# OpenModemV2_rx.net
KiCad netlist of a schematic drawn in EAGLE
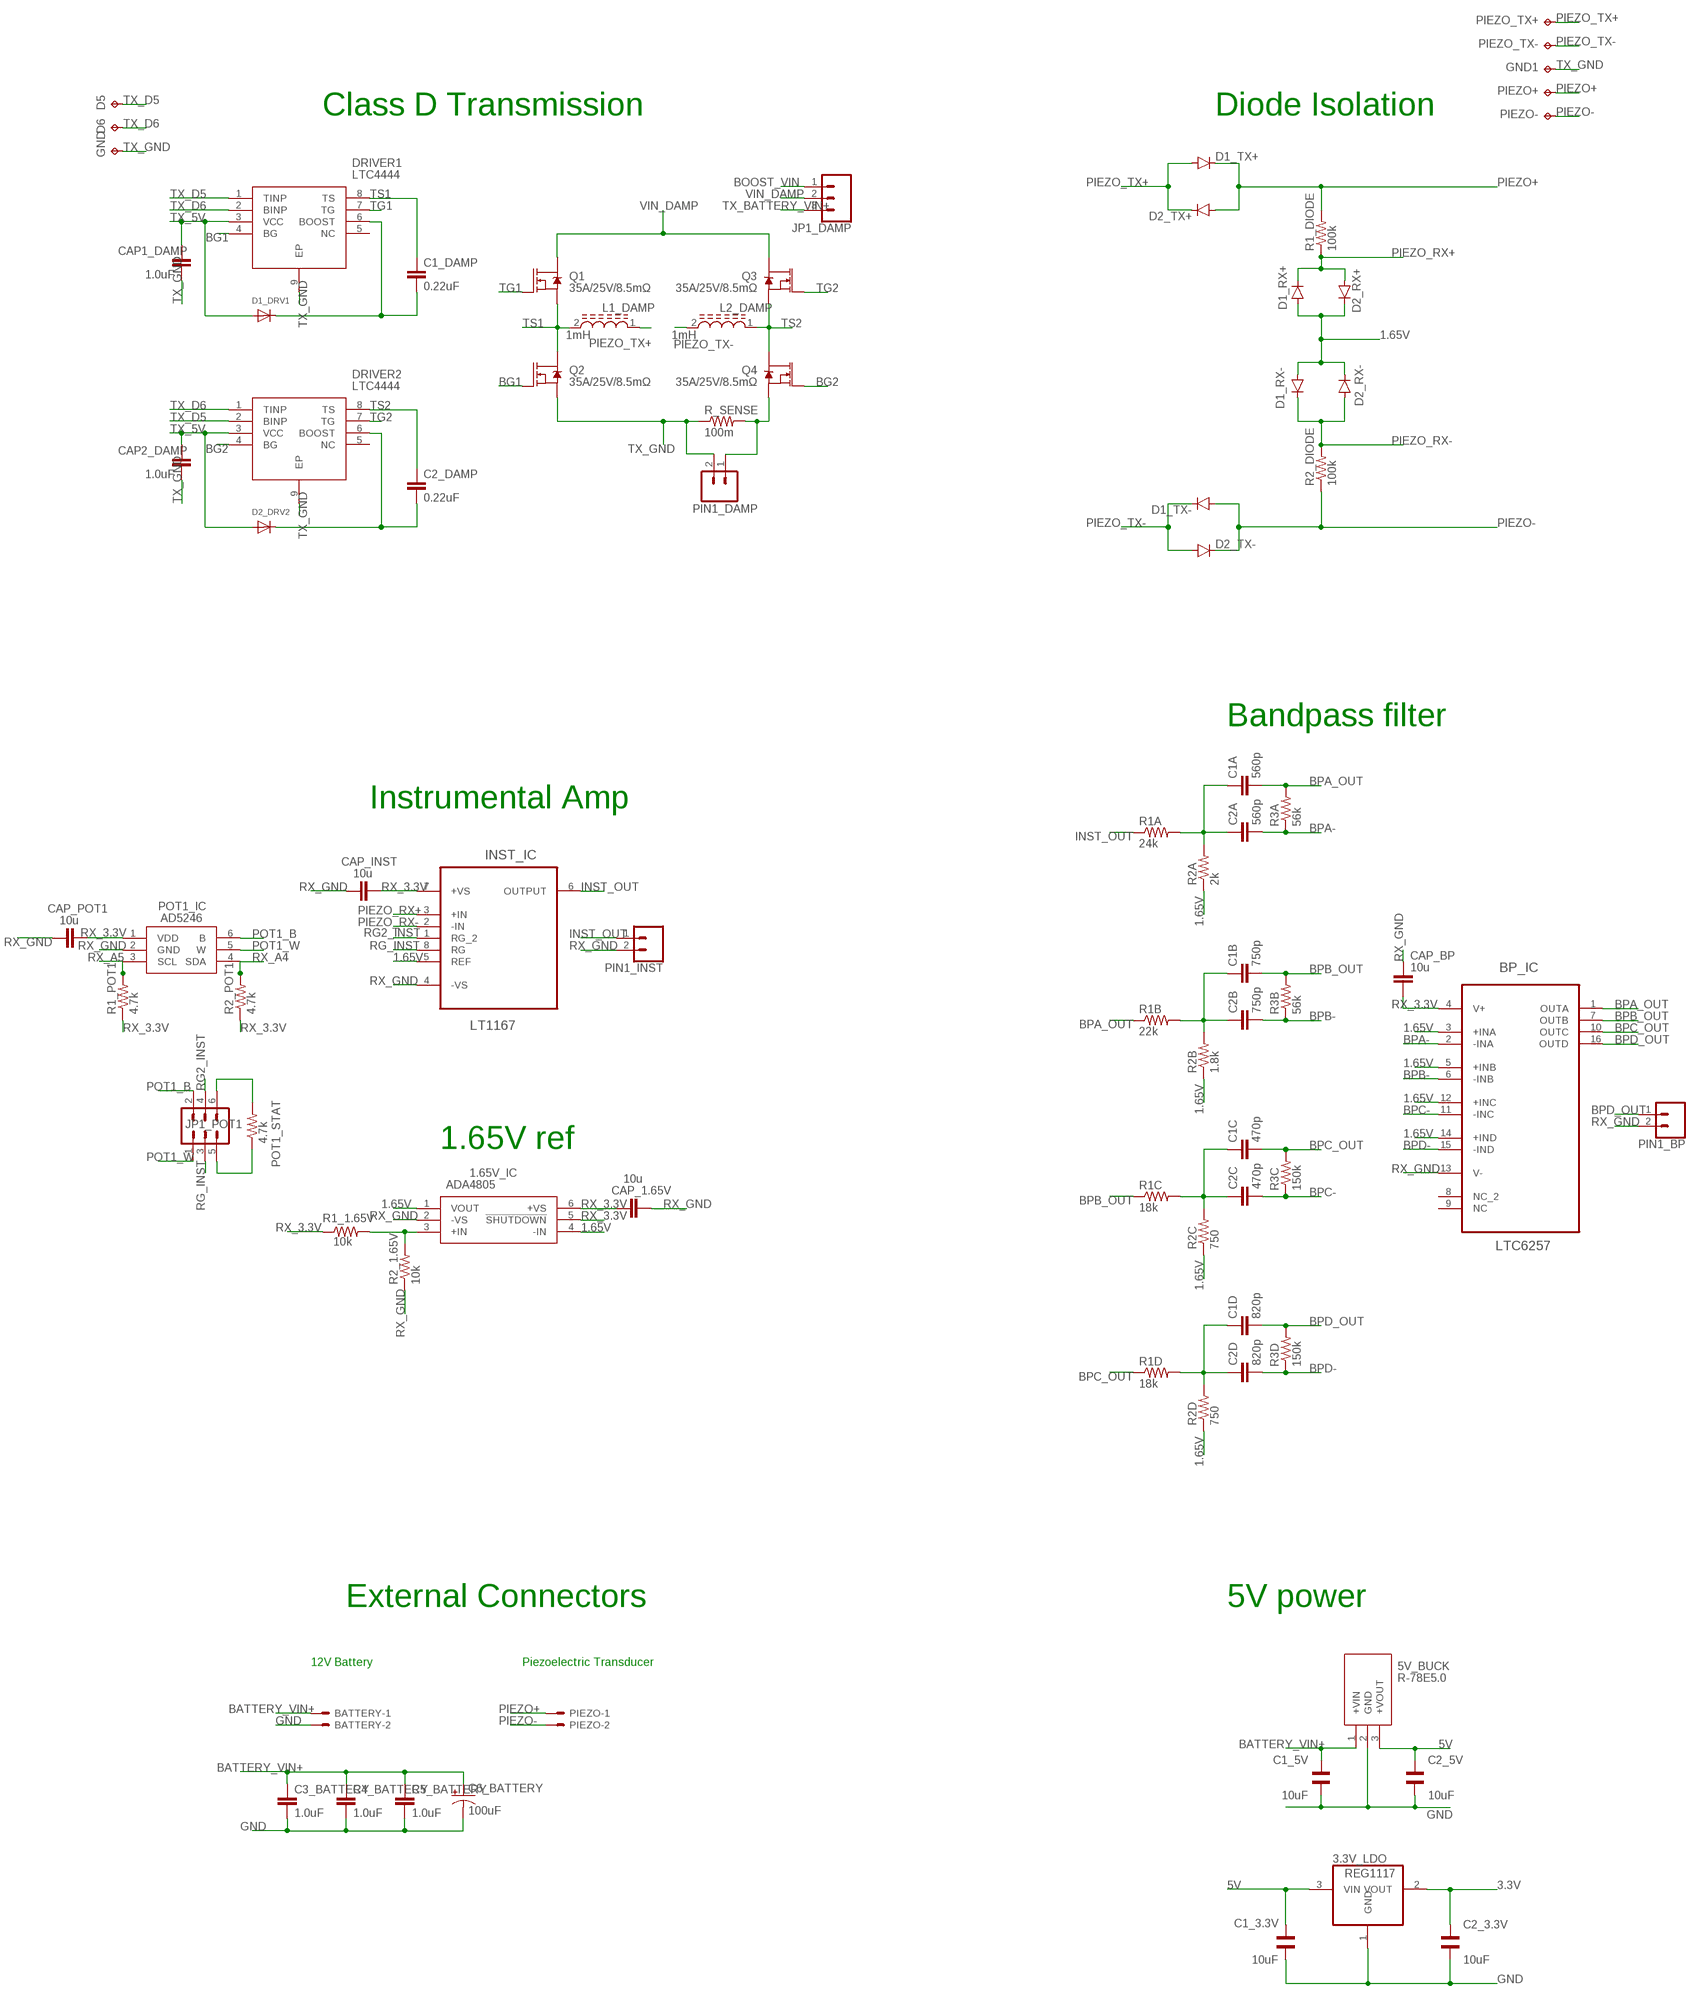
[diagram p0: schematic, sheet 1, part 1 of 2]
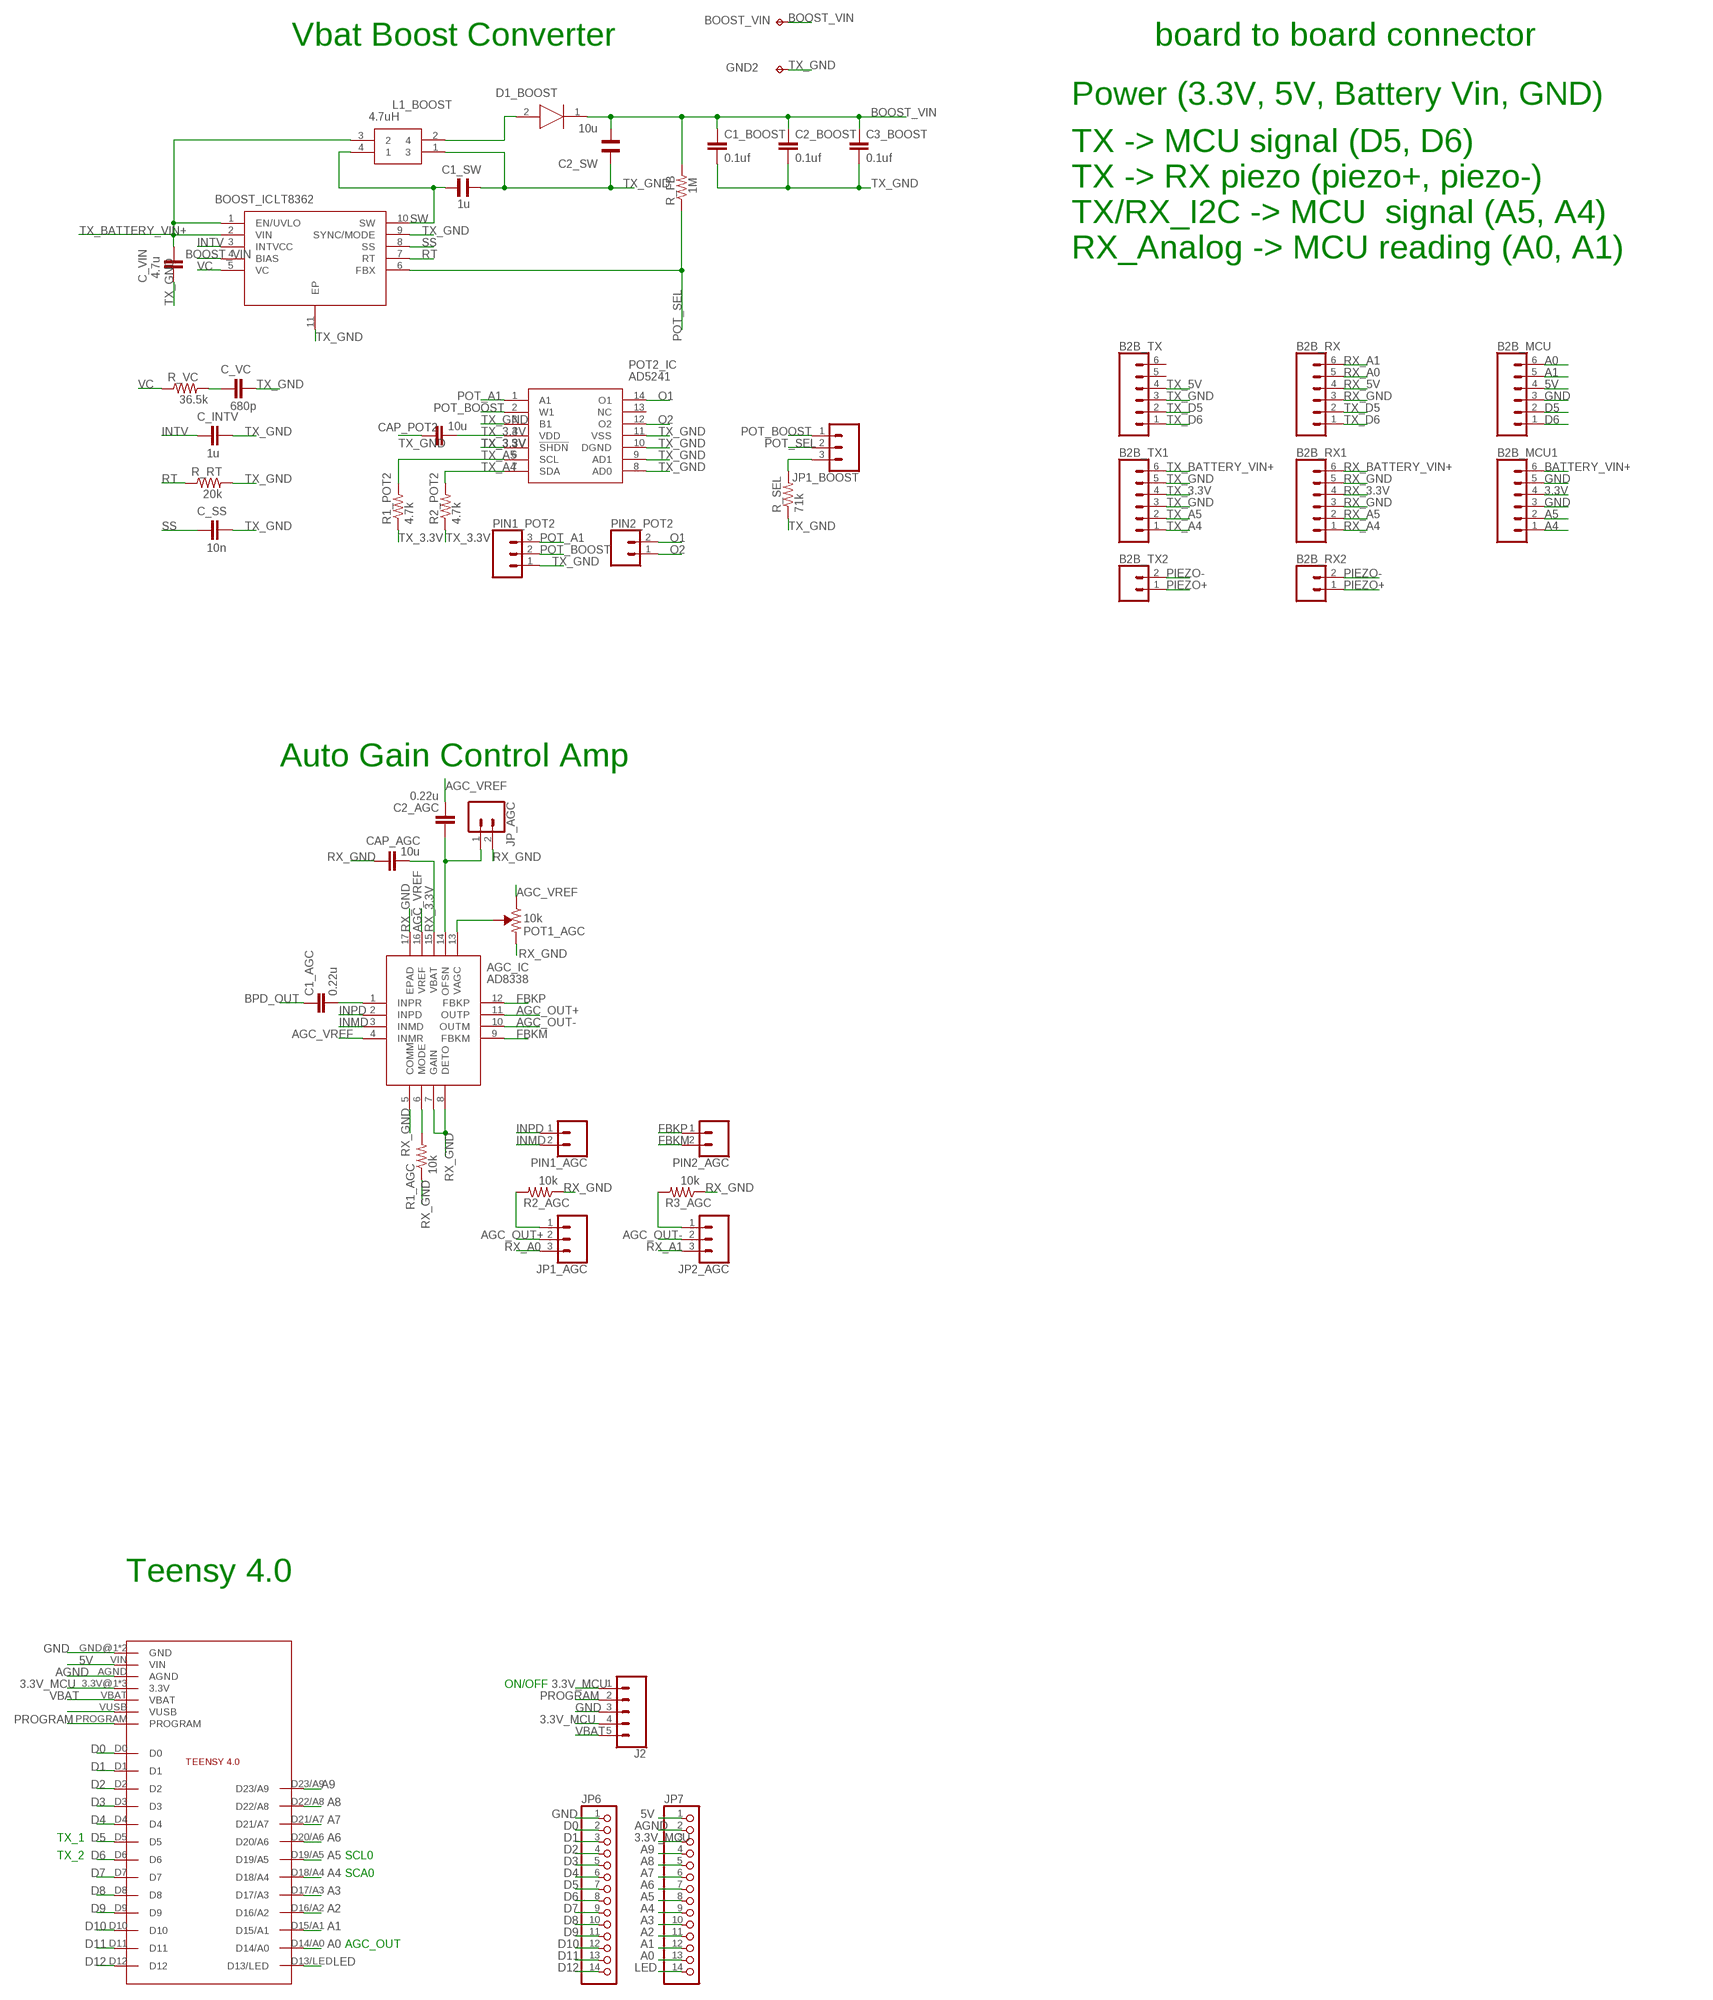
[diagram p1: schematic, sheet 1, part 2 of 2]

(export (version "E")
  (design (tool "Eeschema 10.0.6"))
  (components
    (comp (ref "1.65V_IC")
      (value "ADA4805")
      (footprint "eagle-import:SOT95P280X145-6N")
      (fields
        (field (name "MANUFACTURER_PART_NUMBER") "ADA4805-1ARJZ-R7")
        (field (name "MOUSER_PART_NUMBER") "584-ADA4805-1ARJZ-R7")
      )
      (libsource (lib "eagle-import") (part "ADA4805-1ARJZ-R7"))
    )
    (comp (ref "3.3V_LDO")
      (value "REG1117")
      (footprint "eagle-import:SOT223")
      (libsource (lib "eagle-import") (part "REG1117"))
    )
    (comp (ref "5V_BUCK")
      (value "R-78E5.0")
      (footprint "eagle-import:R-78E5.0-1.0")
      (fields
        (field (name "MANUFACTURER_PART_NUMBER") "R-78E5.0-1.0")
        (field (name "MOUSER_PART_NUMBER") "919-R-78E5.0-1.0")
      )
      (libsource (lib "eagle-import") (part "R-78E5.0-1.0"))
    )
    (comp (ref "AGC_IC")
      (value "AD8338")
      (footprint "eagle-import:QFN50P300X300X80-17N")
      (fields
        (field (name "MANUFACTURER_PART_NUMBER") "AD8338ACPZ-R7")
        (field (name "MOUSER_PART_NUMBER") "584-AD8338ACPZ-R7")
      )
      (libsource (lib "eagle-import") (part "AD8338ACPZ-R7"))
    )
    (comp (ref "B2B_MCU")
      (value "CONN_06SILK_FEMALE_PTH")
      (footprint "eagle-import:1X06")
      (libsource (lib "eagle-import") (part "CONN_06SILK_FEMALE_PTH"))
    )
    (comp (ref "B2B_MCU1")
      (value "CONN_06SILK_FEMALE_PTH")
      (footprint "eagle-import:1X06")
      (libsource (lib "eagle-import") (part "CONN_06SILK_FEMALE_PTH"))
    )
    (comp (ref "B2B_RX")
      (value "CONN_06SILK_FEMALE_PTH")
      (footprint "eagle-import:1X06")
      (libsource (lib "eagle-import") (part "CONN_06SILK_FEMALE_PTH"))
    )
    (comp (ref "B2B_RX1")
      (value "CONN_06SILK_FEMALE_PTH")
      (footprint "eagle-import:1X06")
      (libsource (lib "eagle-import") (part "CONN_06SILK_FEMALE_PTH"))
    )
    (comp (ref "B2B_RX2")
      (value "CONN_02")
      (footprint "eagle-import:1X02")
      (libsource (lib "eagle-import") (part "CONN_02"))
    )
    (comp (ref "B2B_TX")
      (value "CONN_06SILK_FEMALE_PTH")
      (footprint "eagle-import:1X06")
      (libsource (lib "eagle-import") (part "CONN_06SILK_FEMALE_PTH"))
    )
    (comp (ref "B2B_TX1")
      (value "CONN_06SILK_FEMALE_PTH")
      (footprint "eagle-import:1X06")
      (libsource (lib "eagle-import") (part "CONN_06SILK_FEMALE_PTH"))
    )
    (comp (ref "B2B_TX2")
      (value "CONN_02")
      (footprint "eagle-import:1X02")
      (libsource (lib "eagle-import") (part "CONN_02"))
    )
    (comp (ref "BATTERY")
      (value "22-27-2021-02")
      (footprint "eagle-import:6410-02")
      (fields (field (name "MF") "MOLEX"))
      (libsource (lib "eagle-import") (part "22-?-0227-2021"))
    )
    (comp (ref "BOOST_IC")
      (value "LT8362")
      (footprint "eagle-import:SON50P300X300X80-11N")
      (fields
        (field (name "MANUFACTURER_PART_NUMBER") "LT8362EDD#PBF")
        (field (name "MOUSER_PART_NUMBER") "584-LT8362EDDPBF")
      )
      (libsource (lib "eagle-import") (part "LT8362EDD#PBF"))
    )
    (comp (ref "BOOST_VIN")
      (value "TPPAD1-13")
      (footprint "eagle-import:P1-13")
      (libsource (lib "eagle-import") (part "TPPAD1-13"))
    )
    (comp (ref "BP_IC")
      (value "LTC6257")
      (footprint "eagle-import:SOP50P490X110-16N")
      (fields (field (name "MPN") "LTC6257CMS#PBF"))
      (libsource (lib "eagle-import") (part "LTC6257CMSPBF"))
    )
    (comp (ref "C1A")
      (value "560p")
      (footprint "eagle-import:C0402")
      (libsource (lib "eagle-import") (part "CC0402"))
    )
    (comp (ref "C1B")
      (value "750p")
      (footprint "eagle-import:C0402")
      (libsource (lib "eagle-import") (part "CC0402"))
    )
    (comp (ref "C1C")
      (value "470p")
      (footprint "eagle-import:C0402")
      (libsource (lib "eagle-import") (part "CC0402"))
    )
    (comp (ref "C1D")
      (value "820p")
      (footprint "eagle-import:C0402")
      (libsource (lib "eagle-import") (part "CC0402"))
    )
    (comp (ref "C1_3.3V")
      (value "10uF")
      (footprint "eagle-import:WCAP-CSGP_0603_REFLOW")
      (libsource (lib "eagle-import") (part "WCAP-CSGP_0603_REFLOW_885012006001"))
    )
    (comp (ref "C1_5V")
      (value "10uF")
      (footprint "eagle-import:WCAP-CSGP_0603_REFLOW")
      (libsource (lib "eagle-import") (part "WCAP-CSGP_0603_REFLOW_885012006001"))
    )
    (comp (ref "C1_AGC")
      (value "0.22u")
      (footprint "eagle-import:C0402")
      (libsource (lib "eagle-import") (part "CC0402"))
    )
    (comp (ref "C1_BOOST")
      (value "0.1uf")
      (footprint "eagle-import:0805")
      (libsource (lib "eagle-import") (part "1.0UF-0805-25V-(+80/-20%)"))
    )
    (comp (ref "C1_DAMP")
      (value "0.22uF")
      (footprint "eagle-import:0603")
      (libsource (lib "eagle-import") (part "0.22UF-0603-25V-10%"))
    )
    (comp (ref "C1_SW")
      (value "1u")
      (footprint "eagle-import:WCAP-CSGP_1206")
      (libsource (lib "eagle-import") (part "WCAP-CSGP_1206_885012008001"))
    )
    (comp (ref "C2A")
      (value "560p")
      (footprint "eagle-import:C0402")
      (libsource (lib "eagle-import") (part "CC0402"))
    )
    (comp (ref "C2B")
      (value "750p")
      (footprint "eagle-import:C0402")
      (libsource (lib "eagle-import") (part "CC0402"))
    )
    (comp (ref "C2C")
      (value "470p")
      (footprint "eagle-import:C0402")
      (libsource (lib "eagle-import") (part "CC0402"))
    )
    (comp (ref "C2D")
      (value "820p")
      (footprint "eagle-import:C0402")
      (libsource (lib "eagle-import") (part "CC0402"))
    )
    (comp (ref "C2_3.3V")
      (value "10uF")
      (footprint "eagle-import:WCAP-CSGP_0603_REFLOW")
      (libsource (lib "eagle-import") (part "WCAP-CSGP_0603_REFLOW_885012006001"))
    )
    (comp (ref "C2_5V")
      (value "10uF")
      (footprint "eagle-import:WCAP-CSGP_0603_REFLOW")
      (libsource (lib "eagle-import") (part "WCAP-CSGP_0603_REFLOW_885012006001"))
    )
    (comp (ref "C2_AGC")
      (value "0.22u")
      (footprint "eagle-import:C0402")
      (libsource (lib "eagle-import") (part "CC0402"))
    )
    (comp (ref "C2_BOOST")
      (value "0.1uf")
      (footprint "eagle-import:0805")
      (libsource (lib "eagle-import") (part "1.0UF-0805-25V-(+80/-20%)"))
    )
    (comp (ref "C2_DAMP")
      (value "0.22uF")
      (footprint "eagle-import:0603")
      (libsource (lib "eagle-import") (part "0.22UF-0603-25V-10%"))
    )
    (comp (ref "C2_SW")
      (value "10u")
      (footprint "eagle-import:WCAP-CSGP_1206")
      (libsource (lib "eagle-import") (part "WCAP-CSGP_1206_885012008001"))
    )
    (comp (ref "C3_BATTERY")
      (value "1.0uF")
      (footprint "eagle-import:0805")
      (libsource (lib "eagle-import") (part "1.0UF-0805-25V-(+80/-20%)"))
    )
    (comp (ref "C3_BOOST")
      (value "0.1uf")
      (footprint "eagle-import:0805")
      (libsource (lib "eagle-import") (part "1.0UF-0805-25V-(+80/-20%)"))
    )
    (comp (ref "C4_BATTERY")
      (value "1.0uF")
      (footprint "eagle-import:0805")
      (libsource (lib "eagle-import") (part "1.0UF-0805-25V-(+80/-20%)"))
    )
    (comp (ref "C5_BATTERY")
      (value "1.0uF")
      (footprint "eagle-import:0805")
      (libsource (lib "eagle-import") (part "1.0UF-0805-25V-(+80/-20%)"))
    )
    (comp (ref "C6_BATTERY")
      (value "100uF")
      (footprint "eagle-import:PANASONIC_D")
      (libsource (lib "eagle-import") (part "100UF-POLAR-25V-20%(ELEC)"))
    )
    (comp (ref "CAP1_DAMP")
      (value "1.0uF")
      (footprint "eagle-import:0603")
      (libsource (lib "eagle-import") (part "1.0UF-0603-16V-10%"))
    )
    (comp (ref "CAP2_DAMP")
      (value "1.0uF")
      (footprint "eagle-import:0603")
      (libsource (lib "eagle-import") (part "1.0UF-0603-16V-10%"))
    )
    (comp (ref "CAP_1.65V")
      (value "10u")
      (footprint "eagle-import:C0402")
      (libsource (lib "eagle-import") (part "CC0402"))
    )
    (comp (ref "CAP_AGC")
      (value "10u")
      (footprint "eagle-import:C0402")
      (libsource (lib "eagle-import") (part "CC0402"))
    )
    (comp (ref "CAP_BP")
      (value "10u")
      (footprint "eagle-import:C0402")
      (libsource (lib "eagle-import") (part "CC0402"))
    )
    (comp (ref "CAP_INST")
      (value "10u")
      (footprint "eagle-import:C0402")
      (libsource (lib "eagle-import") (part "CC0402"))
    )
    (comp (ref "CAP_POT1")
      (value "10u")
      (footprint "eagle-import:C0402")
      (libsource (lib "eagle-import") (part "CC0402"))
    )
    (comp (ref "CAP_POT2")
      (value "10u")
      (footprint "eagle-import:C0402")
      (libsource (lib "eagle-import") (part "CC0402"))
    )
    (comp (ref "C_INTV")
      (value "1u")
      (footprint "eagle-import:C0402")
      (libsource (lib "eagle-import") (part "CC0402"))
    )
    (comp (ref "C_SS")
      (value "10n")
      (footprint "eagle-import:C0402")
      (libsource (lib "eagle-import") (part "CC0402"))
    )
    (comp (ref "C_VC")
      (value "680p")
      (footprint "eagle-import:C0402")
      (libsource (lib "eagle-import") (part "CC0402"))
    )
    (comp (ref "C_VIN")
      (value "4.7u")
      (footprint "eagle-import:C0402")
      (libsource (lib "eagle-import") (part "CC0402"))
    )
    (comp (ref "D1_BOOST")
      (value "DFLS260-7")
      (footprint "eagle-import:POWERDI123")
      (fields (field (name "MOUSER_PART_NUMBER") "621-DFLS260-7"))
      (libsource (lib "eagle-import") (part "DFLS260-7"))
    )
    (comp (ref "D1_DRV1")
      (value "DIODESOD-323F")
      (footprint "eagle-import:SOD-323F")
      (libsource (lib "eagle-import") (part "DIODESOD-323F"))
    )
    (comp (ref "D1_RX+")
      (value "DIODE-SOD523")
      (footprint "eagle-import:SOD523")
      (libsource (lib "eagle-import") (part "DIODE-SOD523"))
    )
    (comp (ref "D1_RX-")
      (value "DIODE-SOD523")
      (footprint "eagle-import:SOD523")
      (libsource (lib "eagle-import") (part "DIODE-SOD523"))
    )
    (comp (ref "D1_TX+")
      (value "DIODE-SOD523")
      (footprint "eagle-import:SOD523")
      (libsource (lib "eagle-import") (part "DIODE-SOD523"))
    )
    (comp (ref "D1_TX-")
      (value "DIODE-SOD523")
      (footprint "eagle-import:SOD523")
      (libsource (lib "eagle-import") (part "DIODE-SOD523"))
    )
    (comp (ref "D2_DRV2")
      (value "DIODESOD-323F")
      (footprint "eagle-import:SOD-323F")
      (libsource (lib "eagle-import") (part "DIODESOD-323F"))
    )
    (comp (ref "D2_RX+")
      (value "DIODE-SOD523")
      (footprint "eagle-import:SOD523")
      (libsource (lib "eagle-import") (part "DIODE-SOD523"))
    )
    (comp (ref "D2_RX-")
      (value "DIODE-SOD523")
      (footprint "eagle-import:SOD523")
      (libsource (lib "eagle-import") (part "DIODE-SOD523"))
    )
    (comp (ref "D2_TX+")
      (value "DIODE-SOD523")
      (footprint "eagle-import:SOD523")
      (libsource (lib "eagle-import") (part "DIODE-SOD523"))
    )
    (comp (ref "D2_TX-")
      (value "DIODE-SOD523")
      (footprint "eagle-import:SOD523")
      (libsource (lib "eagle-import") (part "DIODE-SOD523"))
    )
    (comp (ref "D5")
      (value "TPPAD1-13")
      (footprint "eagle-import:P1-13")
      (libsource (lib "eagle-import") (part "TPPAD1-13"))
    )
    (comp (ref "D6")
      (value "TPPAD1-13")
      (footprint "eagle-import:P1-13")
      (libsource (lib "eagle-import") (part "TPPAD1-13"))
    )
    (comp (ref "DRIVER1")
      (value "LTC4444")
      (footprint "eagle-import:SOP65P490X110-9N")
      (fields
        (field (name "MANUFACTURER_PART_NUMBER") "LTC4444IMS8E-5#PBF")
        (field (name "MOUSER_PART_NUMBER") "584-C4444IMS8E-5PBF")
      )
      (libsource (lib "eagle-import") (part "LTC4444IMS8E-5#PBF"))
    )
    (comp (ref "DRIVER2")
      (value "LTC4444")
      (footprint "eagle-import:SOP65P490X110-9N")
      (fields
        (field (name "MANUFACTURER_PART_NUMBER") "LTC4444IMS8E-5#PBF")
        (field (name "MOUSER_PART_NUMBER") "584-C4444IMS8E-5PBF")
      )
      (libsource (lib "eagle-import") (part "LTC4444IMS8E-5#PBF"))
    )
    (comp (ref "GND")
      (value "TPPAD1-13")
      (footprint "eagle-import:P1-13")
      (libsource (lib "eagle-import") (part "TPPAD1-13"))
    )
    (comp (ref "GND1")
      (value "TPPAD1-13")
      (footprint "eagle-import:P1-13")
      (libsource (lib "eagle-import") (part "TPPAD1-13"))
    )
    (comp (ref "GND2")
      (value "TPPAD1-13")
      (footprint "eagle-import:P1-13")
      (libsource (lib "eagle-import") (part "TPPAD1-13"))
    )
    (comp (ref "INST_IC")
      (value "LT1167")
      (footprint "eagle-import:SOIC127P600X175-8N")
      (fields (field (name "MPN") "LT1167AIS8#PBF"))
      (libsource (lib "eagle-import") (part "LT1167AIS8PBF"))
    )
    (comp (ref "J2")
      (value "CONN_05")
      (footprint "eagle-import:1X05")
      (libsource (lib "eagle-import") (part "CONN_05"))
    )
    (comp (ref "JP1_AGC")
      (value "CONN_03")
      (footprint "eagle-import:1X03")
      (libsource (lib "eagle-import") (part "CONN_03"))
    )
    (comp (ref "JP1_BOOST")
      (value "CONN_03")
      (footprint "eagle-import:1X03")
      (libsource (lib "eagle-import") (part "CONN_03"))
    )
    (comp (ref "JP1_DAMP")
      (value "CONN_03")
      (footprint "eagle-import:1X03")
      (libsource (lib "eagle-import") (part "CONN_03"))
    )
    (comp (ref "JP1_POT1")
      (value "CONN_03X2NO_SILK")
      (footprint "eagle-import:2X3-NS")
      (libsource (lib "eagle-import") (part "CONN_03X2NO_SILK"))
    )
    (comp (ref "JP2_AGC")
      (value "CONN_03")
      (footprint "eagle-import:1X03")
      (libsource (lib "eagle-import") (part "CONN_03"))
    )
    (comp (ref "JP6")
      (value "PINHD-1X14-CB")
      (footprint "eagle-import:1X14-CB")
      (libsource (lib "eagle-import") (part "PINHD-1X14-CB"))
    )
    (comp (ref "JP7")
      (value "PINHD-1X14-CB")
      (footprint "eagle-import:1X14-CB")
      (libsource (lib "eagle-import") (part "PINHD-1X14-CB"))
    )
    (comp (ref "JP_AGC")
      (value "CONN_02")
      (footprint "eagle-import:1X02")
      (libsource (lib "eagle-import") (part "CONN_02"))
    )
    (comp (ref "L1_BOOST")
      (value "4.7uH")
      (footprint "eagle-import:WE-DD_7332_734512")
      (fields
        (field (name "MANUFACTURER_PART_NUMBER") "744878004")
        (field (name "MOUSER_PART_NUMBER") "710-744878004")
      )
      (libsource (lib "eagle-import") (part "744878004"))
    )
    (comp (ref "L1_DAMP")
      (value "1mH")
      (footprint "eagle-import:INDP125125X600N")
      (fields
        (field (name "DIGI-KEY_PART_NUMBER") "SRR1260-102KCT-ND")
        (field (name "MF") "Bourns")
        (field (name "MP") "SRR1260-102K")
      )
      (libsource (lib "eagle-import") (part "SRR1260-102K"))
    )
    (comp (ref "L2_DAMP")
      (value "1mH")
      (footprint "eagle-import:INDP125125X600N")
      (fields
        (field (name "DIGI-KEY_PART_NUMBER") "SRR1260-102KCT-ND")
        (field (name "MF") "Bourns")
        (field (name "MP") "SRR1260-102K")
      )
      (libsource (lib "eagle-import") (part "SRR1260-102K"))
    )
    (comp (ref "PIEZO")
      (value "22-27-2021-02")
      (footprint "eagle-import:6410-02")
      (fields (field (name "MF") "MOLEX"))
      (libsource (lib "eagle-import") (part "22-?-0227-2021"))
    )
    (comp (ref "PIEZO+")
      (value "TPPAD1-13")
      (footprint "eagle-import:P1-13")
      (libsource (lib "eagle-import") (part "TPPAD1-13"))
    )
    (comp (ref "PIEZO-")
      (value "TPPAD1-13")
      (footprint "eagle-import:P1-13")
      (libsource (lib "eagle-import") (part "TPPAD1-13"))
    )
    (comp (ref "PIEZO_TX+")
      (value "TPPAD1-13")
      (footprint "eagle-import:P1-13")
      (libsource (lib "eagle-import") (part "TPPAD1-13"))
    )
    (comp (ref "PIEZO_TX-")
      (value "TPPAD1-13")
      (footprint "eagle-import:P1-13")
      (libsource (lib "eagle-import") (part "TPPAD1-13"))
    )
    (comp (ref "PIN1_AGC")
      (value "CONN_02")
      (footprint "eagle-import:1X02")
      (libsource (lib "eagle-import") (part "CONN_02"))
    )
    (comp (ref "PIN1_BP")
      (value "CONN_02")
      (footprint "eagle-import:1X02")
      (libsource (lib "eagle-import") (part "CONN_02"))
    )
    (comp (ref "PIN1_DAMP")
      (value "CONN_02")
      (footprint "eagle-import:1X02")
      (libsource (lib "eagle-import") (part "CONN_02"))
    )
    (comp (ref "PIN1_INST")
      (value "CONN_02")
      (footprint "eagle-import:1X02")
      (libsource (lib "eagle-import") (part "CONN_02"))
    )
    (comp (ref "PIN1_POT2")
      (value "CONN_03")
      (footprint "eagle-import:1X03")
      (libsource (lib "eagle-import") (part "CONN_03"))
    )
    (comp (ref "PIN2_AGC")
      (value "CONN_02")
      (footprint "eagle-import:1X02")
      (libsource (lib "eagle-import") (part "CONN_02"))
    )
    (comp (ref "PIN2_POT2")
      (value "CONN_02")
      (footprint "eagle-import:1X02")
      (libsource (lib "eagle-import") (part "CONN_02"))
    )
    (comp (ref "POT1_AGC")
      (value "10k")
      (footprint "eagle-import:TRIMPOT-SMD-3MM-CLOSED")
      (libsource (lib "eagle-import") (part "TRIMPOT-SMD-3MM-CLOSED-1/8W-20%"))
    )
    (comp (ref "POT1_IC")
      (value "AD5246")
      (footprint "eagle-import:SOT65P210X110-6N")
      (fields
        (field (name "MANUFACTURER_PART_NUMBER") "AD5246BKSZ100-RL7")
        (field (name "MOUSER_PART_NUMBER") "584-AD5246BKSZ100-R7")
      )
      (libsource (lib "eagle-import") (part "AD5246BKSZ100-RL7"))
    )
    (comp (ref "POT1_STAT")
      (value "4.7k")
      (footprint "eagle-import:R0603")
      (libsource (lib "eagle-import") (part "audio amplifier example_970892_R-US_R0603"))
    )
    (comp (ref "POT2_IC")
      (value "AD5241")
      (footprint "eagle-import:SOP65P640X120-14N")
      (fields
        (field (name "MANUFACTURER_PART_NUMBER") "AD5241BRUZ10-R7")
        (field (name "MOUSER_PART_NUMBER") "584-AD5241BRUZ10-R7")
      )
      (libsource (lib "eagle-import") (part "AD5241BRUZ10-R7"))
    )
    (comp (ref "Q1")
      (value "35A/25V/8.5mΩ")
      (footprint "eagle-import:DPAK")
      (libsource (lib "eagle-import") (part "MOSFET-NCH-FDD8780"))
    )
    (comp (ref "Q2")
      (value "35A/25V/8.5mΩ")
      (footprint "eagle-import:DPAK")
      (libsource (lib "eagle-import") (part "MOSFET-NCH-FDD8780"))
    )
    (comp (ref "Q3")
      (value "35A/25V/8.5mΩ")
      (footprint "eagle-import:DPAK")
      (libsource (lib "eagle-import") (part "MOSFET-NCH-FDD8780"))
    )
    (comp (ref "Q4")
      (value "35A/25V/8.5mΩ")
      (footprint "eagle-import:DPAK")
      (libsource (lib "eagle-import") (part "MOSFET-NCH-FDD8780"))
    )
    (comp (ref "R1A")
      (value "24k")
      (footprint "eagle-import:R0603")
      (libsource (lib "eagle-import") (part "audio amplifier example_970892_R-US_R0603"))
    )
    (comp (ref "R1B")
      (value "22k")
      (footprint "eagle-import:R0603")
      (libsource (lib "eagle-import") (part "audio amplifier example_970892_R-US_R0603"))
    )
    (comp (ref "R1C")
      (value "18k")
      (footprint "eagle-import:R0603")
      (libsource (lib "eagle-import") (part "audio amplifier example_970892_R-US_R0603"))
    )
    (comp (ref "R1D")
      (value "18k")
      (footprint "eagle-import:R0603")
      (libsource (lib "eagle-import") (part "audio amplifier example_970892_R-US_R0603"))
    )
    (comp (ref "R1_1.65V")
      (value "10k")
      (footprint "eagle-import:R0603")
      (libsource (lib "eagle-import") (part "audio amplifier example_970892_R-US_R0603"))
    )
    (comp (ref "R1_AGC")
      (value "10k")
      (footprint "eagle-import:R0603")
      (libsource (lib "eagle-import") (part "audio amplifier example_970892_R-US_R0603"))
    )
    (comp (ref "R1_DIODE")
      (value "100k")
      (footprint "eagle-import:R0603")
      (libsource (lib "eagle-import") (part "audio amplifier example_970892_R-US_R0603"))
    )
    (comp (ref "R1_POT1")
      (value "4.7k")
      (footprint "eagle-import:R0603")
      (libsource (lib "eagle-import") (part "audio amplifier example_970892_R-US_R0603"))
    )
    (comp (ref "R1_POT2")
      (value "4.7k")
      (footprint "eagle-import:R0603")
      (libsource (lib "eagle-import") (part "audio amplifier example_970892_R-US_R0603"))
    )
    (comp (ref "R2A")
      (value "2k")
      (footprint "eagle-import:R0603")
      (libsource (lib "eagle-import") (part "audio amplifier example_970892_R-US_R0603"))
    )
    (comp (ref "R2B")
      (value "1.8k")
      (footprint "eagle-import:R0603")
      (libsource (lib "eagle-import") (part "audio amplifier example_970892_R-US_R0603"))
    )
    (comp (ref "R2C")
      (value "750")
      (footprint "eagle-import:R0603")
      (libsource (lib "eagle-import") (part "audio amplifier example_970892_R-US_R0603"))
    )
    (comp (ref "R2D")
      (value "750")
      (footprint "eagle-import:R0603")
      (libsource (lib "eagle-import") (part "audio amplifier example_970892_R-US_R0603"))
    )
    (comp (ref "R2_1.65V")
      (value "10k")
      (footprint "eagle-import:R0603")
      (libsource (lib "eagle-import") (part "audio amplifier example_970892_R-US_R0603"))
    )
    (comp (ref "R2_AGC")
      (value "10k")
      (footprint "eagle-import:R0603")
      (libsource (lib "eagle-import") (part "audio amplifier example_970892_R-US_R0603"))
    )
    (comp (ref "R2_DIODE")
      (value "100k")
      (footprint "eagle-import:R0603")
      (libsource (lib "eagle-import") (part "audio amplifier example_970892_R-US_R0603"))
    )
    (comp (ref "R2_POT1")
      (value "4.7k")
      (footprint "eagle-import:R0603")
      (libsource (lib "eagle-import") (part "audio amplifier example_970892_R-US_R0603"))
    )
    (comp (ref "R2_POT2")
      (value "4.7k")
      (footprint "eagle-import:R0603")
      (libsource (lib "eagle-import") (part "audio amplifier example_970892_R-US_R0603"))
    )
    (comp (ref "R3A")
      (value "56k")
      (footprint "eagle-import:R0603")
      (libsource (lib "eagle-import") (part "audio amplifier example_970892_R-US_R0603"))
    )
    (comp (ref "R3B")
      (value "56k")
      (footprint "eagle-import:R0603")
      (libsource (lib "eagle-import") (part "audio amplifier example_970892_R-US_R0603"))
    )
    (comp (ref "R3C")
      (value "150k")
      (footprint "eagle-import:R0603")
      (libsource (lib "eagle-import") (part "audio amplifier example_970892_R-US_R0603"))
    )
    (comp (ref "R3D")
      (value "150k")
      (footprint "eagle-import:R0603")
      (libsource (lib "eagle-import") (part "audio amplifier example_970892_R-US_R0603"))
    )
    (comp (ref "R3_AGC")
      (value "10k")
      (footprint "eagle-import:R0603")
      (libsource (lib "eagle-import") (part "audio amplifier example_970892_R-US_R0603"))
    )
    (comp (ref "R_FB")
      (value "1M")
      (footprint "eagle-import:R0603")
      (libsource (lib "eagle-import") (part "audio amplifier example_970892_R-US_R0603"))
    )
    (comp (ref "R_RT")
      (value "20k")
      (footprint "eagle-import:R0603")
      (libsource (lib "eagle-import") (part "audio amplifier example_970892_R-US_R0603"))
    )
    (comp (ref "R_SEL")
      (value "71k")
      (footprint "eagle-import:R0603")
      (libsource (lib "eagle-import") (part "audio amplifier example_970892_R-US_R0603"))
    )
    (comp (ref "R_SENSE")
      (value "100m")
      (footprint "eagle-import:M1206")
      (libsource (lib "eagle-import") (part "R-US_M1206"))
    )
    (comp (ref "R_VC")
      (value "36.5k")
      (footprint "eagle-import:R0603")
      (libsource (lib "eagle-import") (part "audio amplifier example_970892_R-US_R0603"))
    )
    (comp (ref "U$1")
      (value "TEENSY4.0")
      (footprint "eagle-import:TEENSY4.0")
      (libsource (lib "eagle-import") (part "TEENSY4.0"))
    )
  )
  (nets
    (net (code "1") (name "1.65V") (class "Default")
      (node (ref "1.65V_IC") (pin "1") (pinfunction "VOUT_1") (pintype "bidirectional"))
      (node (ref "1.65V_IC") (pin "4") (pinfunction "-IN_4") (pintype "bidirectional"))
      (node (ref "BP_IC") (pin "12") (pinfunction "+INC_12") (pintype "input"))
      (node (ref "BP_IC") (pin "14") (pinfunction "+IND_14") (pintype "input"))
      (node (ref "BP_IC") (pin "3") (pinfunction "+INA_3") (pintype "passive"))
      (node (ref "BP_IC") (pin "5") (pinfunction "+INB_5") (pintype "passive"))
      (node (ref "D1_RX+") (pin "A") (pinfunction "A_A") (pintype "passive"))
      (node (ref "D1_RX-") (pin "A") (pinfunction "A_A") (pintype "passive"))
      (node (ref "D2_RX+") (pin "C") (pinfunction "C_C") (pintype "passive"))
      (node (ref "D2_RX-") (pin "C") (pinfunction "C_C") (pintype "passive"))
      (node (ref "INST_IC") (pin "5") (pinfunction "REF_5") (pintype "input"))
      (node (ref "R2A") (pin "1") (pinfunction "1_1") (pintype "passive"))
      (node (ref "R2B") (pin "1") (pinfunction "1_1") (pintype "passive"))
      (node (ref "R2C") (pin "1") (pinfunction "1_1") (pintype "passive"))
      (node (ref "R2D") (pin "1") (pinfunction "1_1") (pintype "passive"))
    )
    (net (code "2") (name "3.3V") (class "Default")
      (node (ref "3.3V_LDO") (pin "2") (pinfunction "VOUT_2") (pintype "output"))
      (node (ref "B2B_MCU1") (pin "4") (pinfunction "4_4") (pintype "passive"))
      (node (ref "C2_3.3V") (pin "2") (pinfunction "2_2") (pintype "passive"))
    )
    (net (code "3") (name "3.3V_MCU") (class "Default")
      (node (ref "J2") (pin "1") (pinfunction "1_1") (pintype "passive"))
      (node (ref "J2") (pin "4") (pinfunction "4_4") (pintype "passive"))
      (node (ref "JP7") (pin "3") (pinfunction "3_3") (pintype "passive"))
      (node (ref "U$1") (pin "3.3V@1") (pinfunction "3.3V_3.3V@1") (pintype "bidirectional"))
      (node (ref "U$1") (pin "3.3V@2") (pinfunction "3.3V_3.3V@2") (pintype "bidirectional"))
      (node (ref "U$1") (pin "ON/OFF") (pinfunction "3.3V_ON/OFF") (pintype "bidirectional"))
    )
    (net (code "4") (name "5V") (class "Default")
      (node (ref "3.3V_LDO") (pin "3") (pinfunction "VIN_3") (pintype "input"))
      (node (ref "5V_BUCK") (pin "3") (pinfunction "+VOUT_3") (pintype "bidirectional"))
      (node (ref "B2B_MCU") (pin "4") (pinfunction "4_4") (pintype "passive"))
      (node (ref "C1_3.3V") (pin "2") (pinfunction "2_2") (pintype "passive"))
      (node (ref "C2_5V") (pin "2") (pinfunction "2_2") (pintype "passive"))
      (node (ref "JP7") (pin "1") (pinfunction "1_1") (pintype "passive"))
      (node (ref "U$1") (pin "VIN") (pinfunction "VIN_VIN") (pintype "bidirectional"))
    )
    (net (code "5") (name "A0") (class "Default")
      (node (ref "B2B_MCU") (pin "6") (pinfunction "6_6") (pintype "passive"))
      (node (ref "JP7") (pin "13") (pinfunction "13_13") (pintype "passive"))
      (node (ref "U$1") (pin "D14/A0") (pinfunction "D14/A0_D14/A0") (pintype "bidirectional"))
    )
    (net (code "6") (name "A1") (class "Default")
      (node (ref "B2B_MCU") (pin "5") (pinfunction "5_5") (pintype "passive"))
      (node (ref "JP7") (pin "12") (pinfunction "12_12") (pintype "passive"))
      (node (ref "U$1") (pin "D15/A1") (pinfunction "D15/A1_D15/A1") (pintype "bidirectional"))
    )
    (net (code "7") (name "A2") (class "Default")
      (node (ref "JP7") (pin "11") (pinfunction "11_11") (pintype "passive"))
      (node (ref "U$1") (pin "D16/A2") (pinfunction "D16/A2_D16/A2") (pintype "bidirectional"))
    )
    (net (code "8") (name "A3") (class "Default")
      (node (ref "JP7") (pin "10") (pinfunction "10_10") (pintype "passive"))
      (node (ref "U$1") (pin "D17/A3") (pinfunction "D17/A3_D17/A3") (pintype "bidirectional"))
    )
    (net (code "9") (name "A4") (class "Default")
      (node (ref "B2B_MCU1") (pin "1") (pinfunction "1_1") (pintype "passive"))
      (node (ref "JP7") (pin "9") (pinfunction "9_9") (pintype "passive"))
      (node (ref "U$1") (pin "D18/A4") (pinfunction "D18/A4_D18/A4") (pintype "bidirectional"))
    )
    (net (code "10") (name "A5") (class "Default")
      (node (ref "B2B_MCU1") (pin "2") (pinfunction "2_2") (pintype "passive"))
      (node (ref "JP7") (pin "8") (pinfunction "8_8") (pintype "passive"))
      (node (ref "U$1") (pin "D19/A5") (pinfunction "D19/A5_D19/A5") (pintype "bidirectional"))
    )
    (net (code "11") (name "A6") (class "Default")
      (node (ref "JP7") (pin "7") (pinfunction "7_7") (pintype "passive"))
      (node (ref "U$1") (pin "D20/A6") (pinfunction "D20/A6_D20/A6") (pintype "bidirectional"))
    )
    (net (code "12") (name "A7") (class "Default")
      (node (ref "JP7") (pin "6") (pinfunction "6_6") (pintype "passive"))
      (node (ref "U$1") (pin "D21/A7") (pinfunction "D21/A7_D21/A7") (pintype "bidirectional"))
    )
    (net (code "13") (name "A8") (class "Default")
      (node (ref "JP7") (pin "5") (pinfunction "5_5") (pintype "passive"))
      (node (ref "U$1") (pin "D22/A8") (pinfunction "D22/A8_D22/A8") (pintype "bidirectional"))
    )
    (net (code "14") (name "A9") (class "Default")
      (node (ref "JP7") (pin "4") (pinfunction "4_4") (pintype "passive"))
      (node (ref "U$1") (pin "D23/A9") (pinfunction "D23/A9_D23/A9") (pintype "bidirectional"))
    )
    (net (code "15") (name "AGC_OUT+") (class "Default")
      (node (ref "AGC_IC") (pin "11") (pinfunction "OUTP_11") (pintype "output"))
      (node (ref "JP1_AGC") (pin "2") (pinfunction "2_2") (pintype "passive"))
    )
    (net (code "16") (name "AGC_OUT-") (class "Default")
      (node (ref "AGC_IC") (pin "10") (pinfunction "OUTM_10") (pintype "output"))
      (node (ref "JP2_AGC") (pin "2") (pinfunction "2_2") (pintype "passive"))
    )
    (net (code "17") (name "AGC_VREF") (class "Default")
      (node (ref "AGC_IC") (pin "16") (pinfunction "VREF_16") (pintype "bidirectional"))
      (node (ref "AGC_IC") (pin "4") (pinfunction "INMR_4") (pintype "input"))
      (node (ref "C2_AGC") (pin "2") (pinfunction "2_2") (pintype "passive"))
      (node (ref "POT1_AGC") (pin "3") (pinfunction "CW_3") (pintype "passive"))
    )
    (net (code "18") (name "AGND") (class "Default")
      (node (ref "JP7") (pin "2") (pinfunction "2_2") (pintype "passive"))
      (node (ref "U$1") (pin "AGND") (pinfunction "AGND_AGND") (pintype "bidirectional"))
    )
    (net (code "19") (name "BATTERY_VIN+") (class "Default")
      (node (ref "5V_BUCK") (pin "1") (pinfunction "+VIN_1") (pintype "bidirectional"))
      (node (ref "B2B_MCU1") (pin "6") (pinfunction "6_6") (pintype "passive"))
      (node (ref "BATTERY") (pin "1") (pinfunction "S_1") (pintype "passive"))
      (node (ref "C1_5V") (pin "1") (pinfunction "1_1") (pintype "passive"))
      (node (ref "C3_BATTERY") (pin "1") (pinfunction "1_1") (pintype "passive"))
      (node (ref "C4_BATTERY") (pin "1") (pinfunction "1_1") (pintype "passive"))
      (node (ref "C5_BATTERY") (pin "1") (pinfunction "1_1") (pintype "passive"))
      (node (ref "C6_BATTERY") (pin "+") (pinfunction "+_+") (pintype "passive"))
    )
    (net (code "20") (name "BG1") (class "Default")
      (node (ref "DRIVER1") (pin "4") (pinfunction "BG_4") (pintype "bidirectional"))
      (node (ref "Q2") (pin "1") (pinfunction "G_1") (pintype "bidirectional"))
    )
    (net (code "21") (name "BG2") (class "Default")
      (node (ref "DRIVER2") (pin "4") (pinfunction "BG_4") (pintype "bidirectional"))
      (node (ref "Q4") (pin "1") (pinfunction "G_1") (pintype "bidirectional"))
    )
    (net (code "22") (name "BOOST_VIN") (class "Default")
      (node (ref "BOOST_IC") (pin "4") (pinfunction "BIAS_4") (pintype "bidirectional"))
      (node (ref "BOOST_VIN") (pin "TP") (pinfunction "TP_TP") (pintype "input"))
      (node (ref "C1_BOOST") (pin "1") (pinfunction "1_1") (pintype "passive"))
      (node (ref "C2_BOOST") (pin "1") (pinfunction "1_1") (pintype "passive"))
      (node (ref "C2_SW") (pin "1") (pinfunction "1_1") (pintype "passive"))
      (node (ref "C3_BOOST") (pin "1") (pinfunction "1_1") (pintype "passive"))
      (node (ref "D1_BOOST") (pin "1") (pinfunction "K_1") (pintype "bidirectional"))
      (node (ref "JP1_DAMP") (pin "1") (pinfunction "1_1") (pintype "passive"))
      (node (ref "R_FB") (pin "2") (pinfunction "2_2") (pintype "passive"))
    )
    (net (code "23") (name "BPA-") (class "Default")
      (node (ref "BP_IC") (pin "2") (pinfunction "-INA_2") (pintype "passive"))
      (node (ref "C2A") (pin "2") (pinfunction "2_2") (pintype "passive"))
      (node (ref "R3A") (pin "1") (pinfunction "1_1") (pintype "passive"))
    )
    (net (code "24") (name "BPA_OUT") (class "Default")
      (node (ref "BP_IC") (pin "1") (pinfunction "OUTA_1") (pintype "passive"))
      (node (ref "C1A") (pin "2") (pinfunction "2_2") (pintype "passive"))
      (node (ref "R1B") (pin "1") (pinfunction "1_1") (pintype "passive"))
      (node (ref "R3A") (pin "2") (pinfunction "2_2") (pintype "passive"))
    )
    (net (code "25") (name "BPB-") (class "Default")
      (node (ref "BP_IC") (pin "6") (pinfunction "-INB_6") (pintype "passive"))
      (node (ref "C2B") (pin "2") (pinfunction "2_2") (pintype "passive"))
      (node (ref "R3B") (pin "1") (pinfunction "1_1") (pintype "passive"))
    )
    (net (code "26") (name "BPB_OUT") (class "Default")
      (node (ref "BP_IC") (pin "7") (pinfunction "OUTB_7") (pintype "output"))
      (node (ref "C1B") (pin "2") (pinfunction "2_2") (pintype "passive"))
      (node (ref "R1C") (pin "1") (pinfunction "1_1") (pintype "passive"))
      (node (ref "R3B") (pin "2") (pinfunction "2_2") (pintype "passive"))
    )
    (net (code "27") (name "BPC-") (class "Default")
      (node (ref "BP_IC") (pin "11") (pinfunction "-INC_11") (pintype "input"))
      (node (ref "C2C") (pin "2") (pinfunction "2_2") (pintype "passive"))
      (node (ref "R3C") (pin "1") (pinfunction "1_1") (pintype "passive"))
    )
    (net (code "28") (name "BPC_OUT") (class "Default")
      (node (ref "BP_IC") (pin "10") (pinfunction "OUTC_10") (pintype "output"))
      (node (ref "C1C") (pin "2") (pinfunction "2_2") (pintype "passive"))
      (node (ref "R1D") (pin "1") (pinfunction "1_1") (pintype "passive"))
      (node (ref "R3C") (pin "2") (pinfunction "2_2") (pintype "passive"))
    )
    (net (code "29") (name "BPD-") (class "Default")
      (node (ref "BP_IC") (pin "15") (pinfunction "-IND_15") (pintype "input"))
      (node (ref "C2D") (pin "2") (pinfunction "2_2") (pintype "passive"))
      (node (ref "R3D") (pin "1") (pinfunction "1_1") (pintype "passive"))
    )
    (net (code "30") (name "BPD_OUT") (class "Default")
      (node (ref "BP_IC") (pin "16") (pinfunction "OUTD_16") (pintype "output"))
      (node (ref "C1D") (pin "2") (pinfunction "2_2") (pintype "passive"))
      (node (ref "C1_AGC") (pin "1") (pinfunction "1_1") (pintype "passive"))
      (node (ref "PIN1_BP") (pin "1") (pinfunction "1_1") (pintype "passive"))
      (node (ref "R3D") (pin "2") (pinfunction "2_2") (pintype "passive"))
    )
    (net (code "31") (name "D0") (class "Default")
      (node (ref "JP6") (pin "2") (pinfunction "2_2") (pintype "passive"))
      (node (ref "U$1") (pin "D0") (pinfunction "D0_D0") (pintype "bidirectional"))
    )
    (net (code "32") (name "D1") (class "Default")
      (node (ref "JP6") (pin "3") (pinfunction "3_3") (pintype "passive"))
      (node (ref "U$1") (pin "D1") (pinfunction "D1_D1") (pintype "bidirectional"))
    )
    (net (code "33") (name "D2") (class "Default")
      (node (ref "JP6") (pin "4") (pinfunction "4_4") (pintype "passive"))
      (node (ref "U$1") (pin "D2") (pinfunction "D2_D2") (pintype "bidirectional"))
    )
    (net (code "34") (name "D3") (class "Default")
      (node (ref "JP6") (pin "5") (pinfunction "5_5") (pintype "passive"))
      (node (ref "U$1") (pin "D3") (pinfunction "D3_D3") (pintype "bidirectional"))
    )
    (net (code "35") (name "D4") (class "Default")
      (node (ref "JP6") (pin "6") (pinfunction "6_6") (pintype "passive"))
      (node (ref "U$1") (pin "D4") (pinfunction "D4_D4") (pintype "bidirectional"))
    )
    (net (code "36") (name "D5") (class "Default")
      (node (ref "B2B_MCU") (pin "2") (pinfunction "2_2") (pintype "passive"))
      (node (ref "JP6") (pin "7") (pinfunction "7_7") (pintype "passive"))
      (node (ref "U$1") (pin "D5") (pinfunction "D5_D5") (pintype "bidirectional"))
    )
    (net (code "37") (name "D6") (class "Default")
      (node (ref "B2B_MCU") (pin "1") (pinfunction "1_1") (pintype "passive"))
      (node (ref "JP6") (pin "8") (pinfunction "8_8") (pintype "passive"))
      (node (ref "U$1") (pin "D6") (pinfunction "D6_D6") (pintype "bidirectional"))
    )
    (net (code "38") (name "D7") (class "Default")
      (node (ref "JP6") (pin "9") (pinfunction "9_9") (pintype "passive"))
      (node (ref "U$1") (pin "D7") (pinfunction "D7_D7") (pintype "bidirectional"))
    )
    (net (code "39") (name "D8") (class "Default")
      (node (ref "JP6") (pin "10") (pinfunction "10_10") (pintype "passive"))
      (node (ref "U$1") (pin "D8") (pinfunction "D8_D8") (pintype "bidirectional"))
    )
    (net (code "40") (name "D9") (class "Default")
      (node (ref "JP6") (pin "11") (pinfunction "11_11") (pintype "passive"))
      (node (ref "U$1") (pin "D9") (pinfunction "D9_D9") (pintype "bidirectional"))
    )
    (net (code "41") (name "D10") (class "Default")
      (node (ref "JP6") (pin "12") (pinfunction "12_12") (pintype "passive"))
      (node (ref "U$1") (pin "D10") (pinfunction "D10_D10") (pintype "bidirectional"))
    )
    (net (code "42") (name "D11") (class "Default")
      (node (ref "JP6") (pin "13") (pinfunction "13_13") (pintype "passive"))
      (node (ref "U$1") (pin "D11") (pinfunction "D11_D11") (pintype "bidirectional"))
    )
    (net (code "43") (name "D12") (class "Default")
      (node (ref "JP6") (pin "14") (pinfunction "14_14") (pintype "passive"))
      (node (ref "U$1") (pin "D12") (pinfunction "D12_D12") (pintype "bidirectional"))
    )
    (net (code "44") (name "FBKM") (class "Default")
      (node (ref "AGC_IC") (pin "9") (pinfunction "FBKM_9") (pintype "bidirectional"))
      (node (ref "PIN2_AGC") (pin "2") (pinfunction "2_2") (pintype "passive"))
    )
    (net (code "45") (name "FBKP") (class "Default")
      (node (ref "AGC_IC") (pin "12") (pinfunction "FBKP_12") (pintype "bidirectional"))
      (node (ref "PIN2_AGC") (pin "1") (pinfunction "1_1") (pintype "passive"))
    )
    (net (code "46") (name "GND") (class "Default")
      (node (ref "3.3V_LDO") (pin "1") (pinfunction "GND_1") (pintype "power_in"))
      (node (ref "5V_BUCK") (pin "2") (pinfunction "GND_2") (pintype "bidirectional"))
      (node (ref "B2B_MCU") (pin "3") (pinfunction "3_3") (pintype "passive"))
      (node (ref "B2B_MCU1") (pin "3") (pinfunction "3_3") (pintype "passive"))
      (node (ref "B2B_MCU1") (pin "5") (pinfunction "5_5") (pintype "passive"))
      (node (ref "BATTERY") (pin "2") (pinfunction "S_2") (pintype "passive"))
      (node (ref "C1_3.3V") (pin "1") (pinfunction "1_1") (pintype "passive"))
      (node (ref "C1_5V") (pin "2") (pinfunction "2_2") (pintype "passive"))
      (node (ref "C2_3.3V") (pin "1") (pinfunction "1_1") (pintype "passive"))
      (node (ref "C2_5V") (pin "1") (pinfunction "1_1") (pintype "passive"))
      (node (ref "C3_BATTERY") (pin "2") (pinfunction "2_2") (pintype "passive"))
      (node (ref "C4_BATTERY") (pin "2") (pinfunction "2_2") (pintype "passive"))
      (node (ref "C5_BATTERY") (pin "2") (pinfunction "2_2") (pintype "passive"))
      (node (ref "C6_BATTERY") (pin "-") (pinfunction "-_-") (pintype "passive"))
      (node (ref "J2") (pin "3") (pinfunction "3_3") (pintype "passive"))
      (node (ref "JP6") (pin "1") (pinfunction "1_1") (pintype "passive"))
      (node (ref "U$1") (pin "GND@1") (pinfunction "GND_GND@1") (pintype "bidirectional"))
      (node (ref "U$1") (pin "GND@2") (pinfunction "GND_GND@2") (pintype "bidirectional"))
    )
    (net (code "47") (name "INMD") (class "Default")
      (node (ref "AGC_IC") (pin "3") (pinfunction "INMD_3") (pintype "input"))
      (node (ref "PIN1_AGC") (pin "2") (pinfunction "2_2") (pintype "passive"))
    )
    (net (code "48") (name "INPD") (class "Default")
      (node (ref "AGC_IC") (pin "2") (pinfunction "INPD_2") (pintype "input"))
      (node (ref "PIN1_AGC") (pin "1") (pinfunction "1_1") (pintype "passive"))
    )
    (net (code "49") (name "INST_OUT") (class "Default")
      (node (ref "INST_IC") (pin "6") (pinfunction "OUTPUT_6") (pintype "output"))
      (node (ref "PIN1_INST") (pin "1") (pinfunction "1_1") (pintype "passive"))
      (node (ref "R1A") (pin "1") (pinfunction "1_1") (pintype "passive"))
    )
    (net (code "50") (name "INTV") (class "Default")
      (node (ref "BOOST_IC") (pin "3") (pinfunction "INTVCC_3") (pintype "bidirectional"))
      (node (ref "C_INTV") (pin "2") (pinfunction "2_2") (pintype "passive"))
    )
    (net (code "51") (name "LED") (class "Default")
      (node (ref "JP7") (pin "14") (pinfunction "14_14") (pintype "passive"))
      (node (ref "U$1") (pin "D13/LED") (pinfunction "D13/LED_D13/LED") (pintype "bidirectional"))
    )
    (net (code "52") (name "Net-(1.65V_IC-+IN)") (class "Default")
      (node (ref "1.65V_IC") (pin "3") (pinfunction "+IN_3") (pintype "bidirectional"))
      (node (ref "R1_1.65V") (pin "2") (pinfunction "2_2") (pintype "passive"))
      (node (ref "R2_1.65V") (pin "2") (pinfunction "2_2") (pintype "passive"))
    )
    (net (code "53") (name "Net-(AGC_IC-INPR)") (class "Default")
      (node (ref "AGC_IC") (pin "1") (pinfunction "INPR_1") (pintype "input"))
      (node (ref "C1_AGC") (pin "2") (pinfunction "2_2") (pintype "passive"))
    )
    (net (code "54") (name "Net-(AGC_IC-MODE)") (class "Default")
      (node (ref "AGC_IC") (pin "6") (pinfunction "MODE_6") (pintype "bidirectional"))
      (node (ref "R1_AGC") (pin "2") (pinfunction "2_2") (pintype "passive"))
    )
    (net (code "55") (name "Net-(AGC_IC-OFSN)") (class "Default")
      (node (ref "AGC_IC") (pin "14") (pinfunction "OFSN_14") (pintype "bidirectional"))
      (node (ref "C2_AGC") (pin "1") (pinfunction "1_1") (pintype "passive"))
      (node (ref "JP_AGC") (pin "1") (pinfunction "1_1") (pintype "passive"))
    )
    (net (code "56") (name "Net-(AGC_IC-VAGC)") (class "Default")
      (node (ref "AGC_IC") (pin "13") (pinfunction "VAGC_13") (pintype "bidirectional"))
      (node (ref "POT1_AGC") (pin "2") (pinfunction "WIPER_2") (pintype "passive"))
    )
    (net (code "57") (name "Net-(C1A-Pad1)") (class "Default")
      (node (ref "C1A") (pin "1") (pinfunction "1_1") (pintype "passive"))
      (node (ref "C2A") (pin "1") (pinfunction "1_1") (pintype "passive"))
      (node (ref "R1A") (pin "2") (pinfunction "2_2") (pintype "passive"))
      (node (ref "R2A") (pin "2") (pinfunction "2_2") (pintype "passive"))
    )
    (net (code "58") (name "Net-(C1B-Pad1)") (class "Default")
      (node (ref "C1B") (pin "1") (pinfunction "1_1") (pintype "passive"))
      (node (ref "C2B") (pin "1") (pinfunction "1_1") (pintype "passive"))
      (node (ref "R1B") (pin "2") (pinfunction "2_2") (pintype "passive"))
      (node (ref "R2B") (pin "2") (pinfunction "2_2") (pintype "passive"))
    )
    (net (code "59") (name "Net-(C1C-Pad1)") (class "Default")
      (node (ref "C1C") (pin "1") (pinfunction "1_1") (pintype "passive"))
      (node (ref "C2C") (pin "1") (pinfunction "1_1") (pintype "passive"))
      (node (ref "R1C") (pin "2") (pinfunction "2_2") (pintype "passive"))
      (node (ref "R2C") (pin "2") (pinfunction "2_2") (pintype "passive"))
    )
    (net (code "60") (name "Net-(C1D-Pad1)") (class "Default")
      (node (ref "C1D") (pin "1") (pinfunction "1_1") (pintype "passive"))
      (node (ref "C2D") (pin "1") (pinfunction "1_1") (pintype "passive"))
      (node (ref "R1D") (pin "2") (pinfunction "2_2") (pintype "passive"))
      (node (ref "R2D") (pin "2") (pinfunction "2_2") (pintype "passive"))
    )
    (net (code "61") (name "Net-(C_VC-Pad2)") (class "Default")
      (node (ref "C_VC") (pin "2") (pinfunction "2_2") (pintype "passive"))
      (node (ref "R_VC") (pin "2") (pinfunction "2_2") (pintype "passive"))
    )
    (net (code "62") (name "Net-(D1_BOOST-A)") (class "Default")
      (node (ref "D1_BOOST") (pin "2") (pinfunction "A_2") (pintype "bidirectional"))
      (node (ref "L1_BOOST") (pin "2") (pinfunction "4_2") (pintype "bidirectional"))
    )
    (net (code "63") (name "Net-(DRIVER1-BOOST)") (class "Default")
      (node (ref "C1_DAMP") (pin "2") (pinfunction "2_2") (pintype "passive"))
      (node (ref "D1_DRV1") (pin "C") (pinfunction "C_C") (pintype "passive"))
      (node (ref "DRIVER1") (pin "6") (pinfunction "BOOST_6") (pintype "bidirectional"))
    )
    (net (code "64") (name "Net-(DRIVER2-BOOST)") (class "Default")
      (node (ref "C2_DAMP") (pin "2") (pinfunction "2_2") (pintype "passive"))
      (node (ref "D2_DRV2") (pin "C") (pinfunction "C_C") (pintype "passive"))
      (node (ref "DRIVER2") (pin "6") (pinfunction "BOOST_6") (pintype "bidirectional"))
    )
    (net (code "65") (name "Net-(JP1_AGC-Pad1)") (class "Default")
      (node (ref "JP1_AGC") (pin "1") (pinfunction "1_1") (pintype "passive"))
      (node (ref "R2_AGC") (pin "2") (pinfunction "2_2") (pintype "passive"))
    )
    (net (code "66") (name "Net-(JP1_BOOST-Pad3)") (class "Default")
      (node (ref "JP1_BOOST") (pin "3") (pinfunction "3_3") (pintype "passive"))
      (node (ref "R_SEL") (pin "2") (pinfunction "2_2") (pintype "passive"))
    )
    (net (code "67") (name "Net-(JP1_POT1-Pad5)") (class "Default")
      (node (ref "JP1_POT1") (pin "5") (pinfunction "5_5") (pintype "bidirectional"))
      (node (ref "POT1_STAT") (pin "1") (pinfunction "1_1") (pintype "passive"))
    )
    (net (code "68") (name "Net-(JP1_POT1-Pad6)") (class "Default")
      (node (ref "JP1_POT1") (pin "6") (pinfunction "6_6") (pintype "bidirectional"))
      (node (ref "POT1_STAT") (pin "2") (pinfunction "2_2") (pintype "passive"))
    )
    (net (code "69") (name "Net-(JP2_AGC-Pad1)") (class "Default")
      (node (ref "JP2_AGC") (pin "1") (pinfunction "1_1") (pintype "passive"))
      (node (ref "R3_AGC") (pin "2") (pinfunction "2_2") (pintype "passive"))
    )
    (net (code "70") (name "Net-(Q4-S)") (class "Default")
      (node (ref "PIN1_DAMP") (pin "1") (pinfunction "1_1") (pintype "passive"))
      (node (ref "Q4") (pin "3") (pinfunction "S_3") (pintype "bidirectional"))
      (node (ref "R_SENSE") (pin "2") (pinfunction "2_2") (pintype "passive"))
    )
    (net (code "71") (name "O1") (class "Default")
      (node (ref "PIN2_POT2") (pin "2") (pinfunction "2_2") (pintype "passive"))
      (node (ref "POT2_IC") (pin "14") (pinfunction "O1_14") (pintype "bidirectional"))
    )
    (net (code "72") (name "O2") (class "Default")
      (node (ref "PIN2_POT2") (pin "1") (pinfunction "1_1") (pintype "passive"))
      (node (ref "POT2_IC") (pin "12") (pinfunction "O2_12") (pintype "bidirectional"))
    )
    (net (code "73") (name "PIEZO+") (class "Default")
      (node (ref "B2B_RX2") (pin "1") (pinfunction "1_1") (pintype "passive"))
      (node (ref "B2B_TX2") (pin "1") (pinfunction "1_1") (pintype "passive"))
      (node (ref "D1_TX+") (pin "C") (pinfunction "C_C") (pintype "passive"))
      (node (ref "D2_TX+") (pin "A") (pinfunction "A_A") (pintype "passive"))
      (node (ref "PIEZO") (pin "1") (pinfunction "S_1") (pintype "passive"))
      (node (ref "PIEZO+") (pin "TP") (pinfunction "TP_TP") (pintype "input"))
      (node (ref "R1_DIODE") (pin "2") (pinfunction "2_2") (pintype "passive"))
    )
    (net (code "74") (name "PIEZO-") (class "Default")
      (node (ref "B2B_RX2") (pin "2") (pinfunction "2_2") (pintype "passive"))
      (node (ref "B2B_TX2") (pin "2") (pinfunction "2_2") (pintype "passive"))
      (node (ref "D1_TX-") (pin "A") (pinfunction "A_A") (pintype "passive"))
      (node (ref "D2_TX-") (pin "C") (pinfunction "C_C") (pintype "passive"))
      (node (ref "PIEZO") (pin "2") (pinfunction "S_2") (pintype "passive"))
      (node (ref "PIEZO-") (pin "TP") (pinfunction "TP_TP") (pintype "input"))
      (node (ref "R2_DIODE") (pin "1") (pinfunction "1_1") (pintype "passive"))
    )
    (net (code "75") (name "PIEZO_RX+") (class "Default")
      (node (ref "D1_RX+") (pin "C") (pinfunction "C_C") (pintype "passive"))
      (node (ref "D2_RX+") (pin "A") (pinfunction "A_A") (pintype "passive"))
      (node (ref "INST_IC") (pin "3") (pinfunction "+IN_3") (pintype "input"))
      (node (ref "R1_DIODE") (pin "1") (pinfunction "1_1") (pintype "passive"))
    )
    (net (code "76") (name "PIEZO_RX-") (class "Default")
      (node (ref "D1_RX-") (pin "C") (pinfunction "C_C") (pintype "passive"))
      (node (ref "D2_RX-") (pin "A") (pinfunction "A_A") (pintype "passive"))
      (node (ref "INST_IC") (pin "2") (pinfunction "-IN_2") (pintype "input"))
      (node (ref "R2_DIODE") (pin "2") (pinfunction "2_2") (pintype "passive"))
    )
    (net (code "77") (name "PIEZO_TX+") (class "Default")
      (node (ref "D1_TX+") (pin "A") (pinfunction "A_A") (pintype "passive"))
      (node (ref "D2_TX+") (pin "C") (pinfunction "C_C") (pintype "passive"))
      (node (ref "L1_DAMP") (pin "1") (pinfunction "1_1") (pintype "passive"))
      (node (ref "PIEZO_TX+") (pin "TP") (pinfunction "TP_TP") (pintype "input"))
    )
    (net (code "78") (name "PIEZO_TX-") (class "Default")
      (node (ref "D1_TX-") (pin "C") (pinfunction "C_C") (pintype "passive"))
      (node (ref "D2_TX-") (pin "A") (pinfunction "A_A") (pintype "passive"))
      (node (ref "L2_DAMP") (pin "2") (pinfunction "2_2") (pintype "passive"))
      (node (ref "PIEZO_TX-") (pin "TP") (pinfunction "TP_TP") (pintype "input"))
    )
    (net (code "79") (name "POT1_B") (class "Default")
      (node (ref "JP1_POT1") (pin "2") (pinfunction "2_2") (pintype "bidirectional"))
      (node (ref "POT1_IC") (pin "6") (pinfunction "B_6") (pintype "bidirectional"))
    )
    (net (code "80") (name "POT1_W") (class "Default")
      (node (ref "JP1_POT1") (pin "1") (pinfunction "1_1") (pintype "bidirectional"))
      (node (ref "POT1_IC") (pin "5") (pinfunction "W_5") (pintype "bidirectional"))
    )
    (net (code "81") (name "POT_A1") (class "Default")
      (node (ref "PIN1_POT2") (pin "3") (pinfunction "3_3") (pintype "passive"))
      (node (ref "POT2_IC") (pin "1") (pinfunction "A1_1") (pintype "bidirectional"))
    )
    (net (code "82") (name "POT_BOOST") (class "Default")
      (node (ref "JP1_BOOST") (pin "1") (pinfunction "1_1") (pintype "passive"))
      (node (ref "PIN1_POT2") (pin "2") (pinfunction "2_2") (pintype "passive"))
      (node (ref "POT2_IC") (pin "2") (pinfunction "W1_2") (pintype "bidirectional"))
    )
    (net (code "83") (name "POT_SEL") (class "Default")
      (node (ref "BOOST_IC") (pin "6") (pinfunction "FBX_6") (pintype "bidirectional"))
      (node (ref "JP1_BOOST") (pin "2") (pinfunction "2_2") (pintype "passive"))
      (node (ref "R_FB") (pin "1") (pinfunction "1_1") (pintype "passive"))
    )
    (net (code "84") (name "PROGRAM") (class "Default")
      (node (ref "J2") (pin "2") (pinfunction "2_2") (pintype "passive"))
      (node (ref "U$1") (pin "PROGRAM") (pinfunction "PROGRAM_PROGRAM") (pintype "bidirectional"))
    )
    (net (code "85") (name "RG2_INST") (class "Default")
      (node (ref "INST_IC") (pin "1") (pinfunction "RG_2_1") (pintype "passive"))
      (node (ref "JP1_POT1") (pin "4") (pinfunction "4_4") (pintype "bidirectional"))
    )
    (net (code "86") (name "RG_INST") (class "Default")
      (node (ref "INST_IC") (pin "8") (pinfunction "RG_8") (pintype "passive"))
      (node (ref "JP1_POT1") (pin "3") (pinfunction "3_3") (pintype "bidirectional"))
    )
    (net (code "87") (name "RT") (class "Default")
      (node (ref "BOOST_IC") (pin "7") (pinfunction "RT_7") (pintype "bidirectional"))
      (node (ref "R_RT") (pin "1") (pinfunction "1_1") (pintype "passive"))
    )
    (net (code "88") (name "RX_3.3V") (class "Default")
      (node (ref "1.65V_IC") (pin "5") (pinfunction "~{SHUTDOWN}_5") (pintype "bidirectional"))
      (node (ref "1.65V_IC") (pin "6") (pinfunction "+VS_6") (pintype "bidirectional"))
      (node (ref "AGC_IC") (pin "15") (pinfunction "VBAT_15") (pintype "bidirectional"))
      (node (ref "B2B_RX1") (pin "4") (pinfunction "4_4") (pintype "passive"))
      (node (ref "BP_IC") (pin "4") (pinfunction "V+_4") (pintype "passive"))
      (node (ref "CAP_1.65V") (pin "2") (pinfunction "2_2") (pintype "passive"))
      (node (ref "CAP_AGC") (pin "1") (pinfunction "1_1") (pintype "passive"))
      (node (ref "CAP_BP") (pin "1") (pinfunction "1_1") (pintype "passive"))
      (node (ref "CAP_INST") (pin "2") (pinfunction "2_2") (pintype "passive"))
      (node (ref "CAP_POT1") (pin "2") (pinfunction "2_2") (pintype "passive"))
      (node (ref "INST_IC") (pin "7") (pinfunction "+VS_7") (pintype "power_in"))
      (node (ref "POT1_IC") (pin "1") (pinfunction "VDD_1") (pintype "bidirectional"))
      (node (ref "R1_1.65V") (pin "1") (pinfunction "1_1") (pintype "passive"))
      (node (ref "R1_POT1") (pin "1") (pinfunction "1_1") (pintype "passive"))
      (node (ref "R2_POT1") (pin "1") (pinfunction "1_1") (pintype "passive"))
    )
    (net (code "89") (name "RX_5V") (class "Default")
      (node (ref "B2B_RX") (pin "4") (pinfunction "4_4") (pintype "passive"))
    )
    (net (code "90") (name "RX_A0") (class "Default")
      (node (ref "B2B_RX") (pin "5") (pinfunction "5_5") (pintype "passive"))
      (node (ref "JP1_AGC") (pin "3") (pinfunction "3_3") (pintype "passive"))
    )
    (net (code "91") (name "RX_A1") (class "Default")
      (node (ref "B2B_RX") (pin "6") (pinfunction "6_6") (pintype "passive"))
      (node (ref "JP2_AGC") (pin "3") (pinfunction "3_3") (pintype "passive"))
    )
    (net (code "92") (name "RX_A4") (class "Default")
      (node (ref "B2B_RX1") (pin "1") (pinfunction "1_1") (pintype "passive"))
      (node (ref "POT1_IC") (pin "4") (pinfunction "SDA_4") (pintype "bidirectional"))
      (node (ref "R2_POT1") (pin "2") (pinfunction "2_2") (pintype "passive"))
    )
    (net (code "93") (name "RX_A5") (class "Default")
      (node (ref "B2B_RX1") (pin "2") (pinfunction "2_2") (pintype "passive"))
      (node (ref "POT1_IC") (pin "3") (pinfunction "SCL_3") (pintype "bidirectional"))
      (node (ref "R1_POT1") (pin "2") (pinfunction "2_2") (pintype "passive"))
    )
    (net (code "94") (name "RX_BATTERY_VIN+") (class "Default")
      (node (ref "B2B_RX1") (pin "6") (pinfunction "6_6") (pintype "passive"))
    )
    (net (code "95") (name "RX_GND") (class "Default")
      (node (ref "1.65V_IC") (pin "2") (pinfunction "-VS_2") (pintype "bidirectional"))
      (node (ref "AGC_IC") (pin "17") (pinfunction "EPAD_17") (pintype "bidirectional"))
      (node (ref "AGC_IC") (pin "5") (pinfunction "COMM_5") (pintype "power_in"))
      (node (ref "AGC_IC") (pin "7") (pinfunction "GAIN_7") (pintype "input"))
      (node (ref "AGC_IC") (pin "8") (pinfunction "DETO_8") (pintype "output"))
      (node (ref "B2B_RX") (pin "3") (pinfunction "3_3") (pintype "passive"))
      (node (ref "B2B_RX1") (pin "3") (pinfunction "3_3") (pintype "passive"))
      (node (ref "B2B_RX1") (pin "5") (pinfunction "5_5") (pintype "passive"))
      (node (ref "BP_IC") (pin "13") (pinfunction "V-_13") (pintype "power_in"))
      (node (ref "CAP_1.65V") (pin "1") (pinfunction "1_1") (pintype "passive"))
      (node (ref "CAP_AGC") (pin "2") (pinfunction "2_2") (pintype "passive"))
      (node (ref "CAP_BP") (pin "2") (pinfunction "2_2") (pintype "passive"))
      (node (ref "CAP_INST") (pin "1") (pinfunction "1_1") (pintype "passive"))
      (node (ref "CAP_POT1") (pin "1") (pinfunction "1_1") (pintype "passive"))
      (node (ref "INST_IC") (pin "4") (pinfunction "-VS_4") (pintype "power_in"))
      (node (ref "JP_AGC") (pin "2") (pinfunction "2_2") (pintype "passive"))
      (node (ref "PIN1_BP") (pin "2") (pinfunction "2_2") (pintype "passive"))
      (node (ref "PIN1_INST") (pin "2") (pinfunction "2_2") (pintype "passive"))
      (node (ref "POT1_AGC") (pin "1") (pinfunction "CCW_1") (pintype "passive"))
      (node (ref "POT1_IC") (pin "2") (pinfunction "GND_2") (pintype "bidirectional"))
      (node (ref "R1_AGC") (pin "1") (pinfunction "1_1") (pintype "passive"))
      (node (ref "R2_1.65V") (pin "1") (pinfunction "1_1") (pintype "passive"))
      (node (ref "R2_AGC") (pin "1") (pinfunction "1_1") (pintype "passive"))
      (node (ref "R3_AGC") (pin "1") (pinfunction "1_1") (pintype "passive"))
    )
    (net (code "96") (name "SS") (class "Default")
      (node (ref "BOOST_IC") (pin "8") (pinfunction "SS_8") (pintype "bidirectional"))
      (node (ref "C_SS") (pin "2") (pinfunction "2_2") (pintype "passive"))
    )
    (net (code "97") (name "SW") (class "Default")
      (node (ref "BOOST_IC") (pin "10") (pinfunction "SW_10") (pintype "bidirectional"))
      (node (ref "C1_SW") (pin "2") (pinfunction "2_2") (pintype "passive"))
      (node (ref "L1_BOOST") (pin "4") (pinfunction "1_4") (pintype "bidirectional"))
    )
    (net (code "98") (name "TG1") (class "Default")
      (node (ref "DRIVER1") (pin "7") (pinfunction "TG_7") (pintype "bidirectional"))
      (node (ref "Q1") (pin "1") (pinfunction "G_1") (pintype "bidirectional"))
    )
    (net (code "99") (name "TG2") (class "Default")
      (node (ref "DRIVER2") (pin "7") (pinfunction "TG_7") (pintype "bidirectional"))
      (node (ref "Q3") (pin "1") (pinfunction "G_1") (pintype "bidirectional"))
    )
    (net (code "100") (name "TS1") (class "Default")
      (node (ref "C1_DAMP") (pin "1") (pinfunction "1_1") (pintype "passive"))
      (node (ref "DRIVER1") (pin "8") (pinfunction "TS_8") (pintype "bidirectional"))
      (node (ref "L1_DAMP") (pin "2") (pinfunction "2_2") (pintype "passive"))
      (node (ref "Q1") (pin "3") (pinfunction "S_3") (pintype "bidirectional"))
      (node (ref "Q2") (pin "4") (pinfunction "D_4") (pintype "bidirectional"))
    )
    (net (code "101") (name "TS2") (class "Default")
      (node (ref "C2_DAMP") (pin "1") (pinfunction "1_1") (pintype "passive"))
      (node (ref "DRIVER2") (pin "8") (pinfunction "TS_8") (pintype "bidirectional"))
      (node (ref "L2_DAMP") (pin "1") (pinfunction "1_1") (pintype "passive"))
      (node (ref "Q3") (pin "3") (pinfunction "S_3") (pintype "bidirectional"))
      (node (ref "Q4") (pin "4") (pinfunction "D_4") (pintype "bidirectional"))
    )
    (net (code "102") (name "TX_3.3V") (class "Default")
      (node (ref "B2B_TX1") (pin "4") (pinfunction "4_4") (pintype "passive"))
      (node (ref "CAP_POT2") (pin "1") (pinfunction "1_1") (pintype "passive"))
      (node (ref "POT2_IC") (pin "4") (pinfunction "VDD_4") (pintype "bidirectional"))
      (node (ref "POT2_IC") (pin "5") (pinfunction "~{SHDN}_5") (pintype "bidirectional"))
      (node (ref "R1_POT2") (pin "1") (pinfunction "1_1") (pintype "passive"))
      (node (ref "R2_POT2") (pin "1") (pinfunction "1_1") (pintype "passive"))
    )
    (net (code "103") (name "TX_5V") (class "Default")
      (node (ref "B2B_TX") (pin "4") (pinfunction "4_4") (pintype "passive"))
      (node (ref "CAP1_DAMP") (pin "1") (pinfunction "1_1") (pintype "passive"))
      (node (ref "CAP2_DAMP") (pin "1") (pinfunction "1_1") (pintype "passive"))
      (node (ref "D1_DRV1") (pin "A") (pinfunction "A_A") (pintype "passive"))
      (node (ref "D2_DRV2") (pin "A") (pinfunction "A_A") (pintype "passive"))
      (node (ref "DRIVER1") (pin "3") (pinfunction "VCC_3") (pintype "power_in"))
      (node (ref "DRIVER2") (pin "3") (pinfunction "VCC_3") (pintype "power_in"))
    )
    (net (code "104") (name "TX_A4") (class "Default")
      (node (ref "B2B_TX1") (pin "1") (pinfunction "1_1") (pintype "passive"))
      (node (ref "POT2_IC") (pin "7") (pinfunction "SDA_7") (pintype "bidirectional"))
      (node (ref "R2_POT2") (pin "2") (pinfunction "2_2") (pintype "passive"))
    )
    (net (code "105") (name "TX_A5") (class "Default")
      (node (ref "B2B_TX1") (pin "2") (pinfunction "2_2") (pintype "passive"))
      (node (ref "POT2_IC") (pin "6") (pinfunction "SCL_6") (pintype "bidirectional"))
      (node (ref "R1_POT2") (pin "2") (pinfunction "2_2") (pintype "passive"))
    )
    (net (code "106") (name "TX_BATTERY_VIN+") (class "Default")
      (node (ref "B2B_TX1") (pin "6") (pinfunction "6_6") (pintype "passive"))
      (node (ref "BOOST_IC") (pin "1") (pinfunction "EN/UVLO_1") (pintype "bidirectional"))
      (node (ref "BOOST_IC") (pin "2") (pinfunction "VIN_2") (pintype "bidirectional"))
      (node (ref "C_VIN") (pin "2") (pinfunction "2_2") (pintype "passive"))
      (node (ref "JP1_DAMP") (pin "3") (pinfunction "3_3") (pintype "passive"))
      (node (ref "L1_BOOST") (pin "3") (pinfunction "2_3") (pintype "bidirectional"))
    )
    (net (code "107") (name "TX_D5") (class "Default")
      (node (ref "B2B_RX") (pin "2") (pinfunction "2_2") (pintype "passive"))
      (node (ref "B2B_TX") (pin "2") (pinfunction "2_2") (pintype "passive"))
      (node (ref "D5") (pin "TP") (pinfunction "TP_TP") (pintype "input"))
      (node (ref "DRIVER1") (pin "1") (pinfunction "TINP_1") (pintype "input"))
      (node (ref "DRIVER2") (pin "2") (pinfunction "BINP_2") (pintype "input"))
    )
    (net (code "108") (name "TX_D6") (class "Default")
      (node (ref "B2B_RX") (pin "1") (pinfunction "1_1") (pintype "passive"))
      (node (ref "B2B_TX") (pin "1") (pinfunction "1_1") (pintype "passive"))
      (node (ref "D6") (pin "TP") (pinfunction "TP_TP") (pintype "input"))
      (node (ref "DRIVER1") (pin "2") (pinfunction "BINP_2") (pintype "input"))
      (node (ref "DRIVER2") (pin "1") (pinfunction "TINP_1") (pintype "input"))
    )
    (net (code "109") (name "TX_GND") (class "Default")
      (node (ref "B2B_TX") (pin "3") (pinfunction "3_3") (pintype "passive"))
      (node (ref "B2B_TX1") (pin "3") (pinfunction "3_3") (pintype "passive"))
      (node (ref "B2B_TX1") (pin "5") (pinfunction "5_5") (pintype "passive"))
      (node (ref "BOOST_IC") (pin "11") (pinfunction "EP_11") (pintype "bidirectional"))
      (node (ref "BOOST_IC") (pin "9") (pinfunction "SYNC/MODE_9") (pintype "bidirectional"))
      (node (ref "C1_BOOST") (pin "2") (pinfunction "2_2") (pintype "passive"))
      (node (ref "C1_SW") (pin "1") (pinfunction "1_1") (pintype "passive"))
      (node (ref "C2_BOOST") (pin "2") (pinfunction "2_2") (pintype "passive"))
      (node (ref "C2_SW") (pin "2") (pinfunction "2_2") (pintype "passive"))
      (node (ref "C3_BOOST") (pin "2") (pinfunction "2_2") (pintype "passive"))
      (node (ref "CAP1_DAMP") (pin "2") (pinfunction "2_2") (pintype "passive"))
      (node (ref "CAP2_DAMP") (pin "2") (pinfunction "2_2") (pintype "passive"))
      (node (ref "CAP_POT2") (pin "2") (pinfunction "2_2") (pintype "passive"))
      (node (ref "C_INTV") (pin "1") (pinfunction "1_1") (pintype "passive"))
      (node (ref "C_SS") (pin "1") (pinfunction "1_1") (pintype "passive"))
      (node (ref "C_VC") (pin "1") (pinfunction "1_1") (pintype "passive"))
      (node (ref "C_VIN") (pin "1") (pinfunction "1_1") (pintype "passive"))
      (node (ref "DRIVER1") (pin "9") (pinfunction "EP_9") (pintype "power_in"))
      (node (ref "DRIVER2") (pin "9") (pinfunction "EP_9") (pintype "power_in"))
      (node (ref "GND") (pin "TP") (pinfunction "TP_TP") (pintype "input"))
      (node (ref "GND1") (pin "TP") (pinfunction "TP_TP") (pintype "input"))
      (node (ref "GND2") (pin "TP") (pinfunction "TP_TP") (pintype "input"))
      (node (ref "L1_BOOST") (pin "1") (pinfunction "3_1") (pintype "bidirectional"))
      (node (ref "PIN1_DAMP") (pin "2") (pinfunction "2_2") (pintype "passive"))
      (node (ref "PIN1_POT2") (pin "1") (pinfunction "1_1") (pintype "passive"))
      (node (ref "POT2_IC") (pin "10") (pinfunction "DGND_10") (pintype "bidirectional"))
      (node (ref "POT2_IC") (pin "11") (pinfunction "VSS_11") (pintype "bidirectional"))
      (node (ref "POT2_IC") (pin "3") (pinfunction "B1_3") (pintype "bidirectional"))
      (node (ref "POT2_IC") (pin "8") (pinfunction "AD0_8") (pintype "bidirectional"))
      (node (ref "POT2_IC") (pin "9") (pinfunction "AD1_9") (pintype "bidirectional"))
      (node (ref "Q2") (pin "3") (pinfunction "S_3") (pintype "bidirectional"))
      (node (ref "R_RT") (pin "2") (pinfunction "2_2") (pintype "passive"))
      (node (ref "R_SEL") (pin "1") (pinfunction "1_1") (pintype "passive"))
      (node (ref "R_SENSE") (pin "1") (pinfunction "1_1") (pintype "passive"))
    )
    (net (code "110") (name "VBAT") (class "Default")
      (node (ref "J2") (pin "5") (pinfunction "5_5") (pintype "passive"))
      (node (ref "U$1") (pin "VBAT") (pinfunction "VBAT_VBAT") (pintype "bidirectional"))
    )
    (net (code "111") (name "VC") (class "Default")
      (node (ref "BOOST_IC") (pin "5") (pinfunction "VC_5") (pintype "bidirectional"))
      (node (ref "R_VC") (pin "1") (pinfunction "1_1") (pintype "passive"))
    )
    (net (code "112") (name "VIN_DAMP") (class "Default")
      (node (ref "JP1_DAMP") (pin "2") (pinfunction "2_2") (pintype "passive"))
      (node (ref "Q1") (pin "4") (pinfunction "D_4") (pintype "bidirectional"))
      (node (ref "Q3") (pin "4") (pinfunction "D_4") (pintype "bidirectional"))
    )
    (net (code "113") (name "unconnected-(B2B_TX-Pad5)") (class "Default")
      (node (ref "B2B_TX") (pin "5") (pinfunction "5_5") (pintype "passive"))
    )
    (net (code "114") (name "unconnected-(B2B_TX-Pad6)") (class "Default")
      (node (ref "B2B_TX") (pin "6") (pinfunction "6_6") (pintype "passive"))
    )
    (net (code "115") (name "unconnected-(BP_IC-NC-Pad9)") (class "Default")
      (node (ref "BP_IC") (pin "9") (pinfunction "NC_9") (pintype "no_connect"))
    )
    (net (code "116") (name "unconnected-(BP_IC-NC_2-Pad8)") (class "Default")
      (node (ref "BP_IC") (pin "8") (pinfunction "NC_2_8") (pintype "no_connect"))
    )
    (net (code "117") (name "unconnected-(DRIVER1-NC-Pad5)") (class "Default")
      (node (ref "DRIVER1") (pin "5") (pinfunction "NC_5") (pintype "no_connect"))
    )
    (net (code "118") (name "unconnected-(DRIVER2-NC-Pad5)") (class "Default")
      (node (ref "DRIVER2") (pin "5") (pinfunction "NC_5") (pintype "no_connect"))
    )
    (net (code "119") (name "unconnected-(POT2_IC-NC-Pad13)") (class "Default")
      (node (ref "POT2_IC") (pin "13") (pinfunction "NC_13") (pintype "no_connect"))
    )
    (net (code "120") (name "unconnected-(U$1-PadVUSB)") (class "Default")
      (node (ref "U$1") (pin "VUSB") (pinfunction "VUSB_VUSB") (pintype "bidirectional"))
    )
  )
)
